# Trevor-th.net
KiCad netlist of a schematic drawn in EAGLE
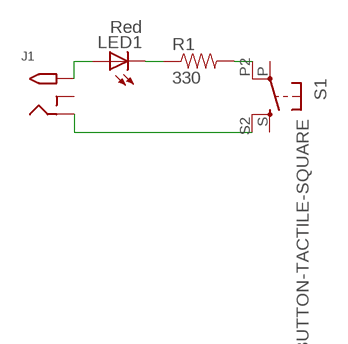
[diagram p0: schematic, sheet 1]

(export (version "E")
  (design (tool "Eeschema 10.0.6"))
  (components
    (comp (ref "J1")
      (value "2.1MMJACKTHM")
      (footprint "eagle-import:PJ-102A")
      (libsource (lib "eagle-import") (part "2.1MMJACKTHM"))
    )
    (comp (ref "LED1")
      (value "Red")
      (footprint "eagle-import:LED5MM")
      (libsource (lib "eagle-import") (part "LED5MM"))
    )
    (comp (ref "R1")
      (value "330")
      (footprint "eagle-import:AXIAL-0.3")
      (libsource (lib "eagle-import") (part "RESISTORAXIAL-0.3"))
    )
    (comp (ref "S1")
      (value "BUTTON-TACTILE-SQUARE")
      (footprint "eagle-import:BUTTON-TACTILE-SQUARE-ADAFRUIT1010")
      (libsource (lib "eagle-import") (part "BUTTON-TACTILE-SQUARE"))
    )
  )
  (nets
    (net (code "1") (name "Net-(J1-PadTIP)") (class "Default")
      (node (ref "J1") (pin "TIP") (pinfunction "TIP_TIP") (pintype "bidirectional"))
      (node (ref "LED1") (pin "A") (pinfunction "A_A") (pintype "passive"))
    )
    (net (code "2") (name "Net-(LED1-C)") (class "Default")
      (node (ref "LED1") (pin "K") (pinfunction "C_K") (pintype "passive"))
      (node (ref "R1") (pin "P$1") (pinfunction "1_P$1") (pintype "passive"))
    )
    (net (code "3") (name "Net-(R1-2)") (class "Default")
      (node (ref "R1") (pin "P$2") (pinfunction "2_P$2") (pintype "passive"))
      (node (ref "S1") (pin "P2") (pinfunction "P1_P2") (pintype "passive"))
    )
    (net (code "4") (name "Net-(S1-S1)") (class "Default")
      (node (ref "J1") (pin "RING") (pinfunction "RING_RING") (pintype "bidirectional"))
      (node (ref "S1") (pin "S2") (pinfunction "S1_S2") (pintype "passive"))
    )
    (net (code "5") (name "unconnected-(J1-PadRING_SW)") (class "Default")
      (node (ref "J1") (pin "RING_SW") (pinfunction "RING_SW_RING_SW") (pintype "bidirectional"))
    )
    (net (code "6") (name "unconnected-(S1-PadP)") (class "Default")
      (node (ref "S1") (pin "P") (pinfunction "P_P") (pintype "passive"))
    )
    (net (code "7") (name "unconnected-(S1-PadS)") (class "Default")
      (node (ref "S1") (pin "S") (pinfunction "S_S") (pintype "passive"))
    )
  )
)
